# Lights.net
KiCad netlist of a schematic drawn in Altium Designer
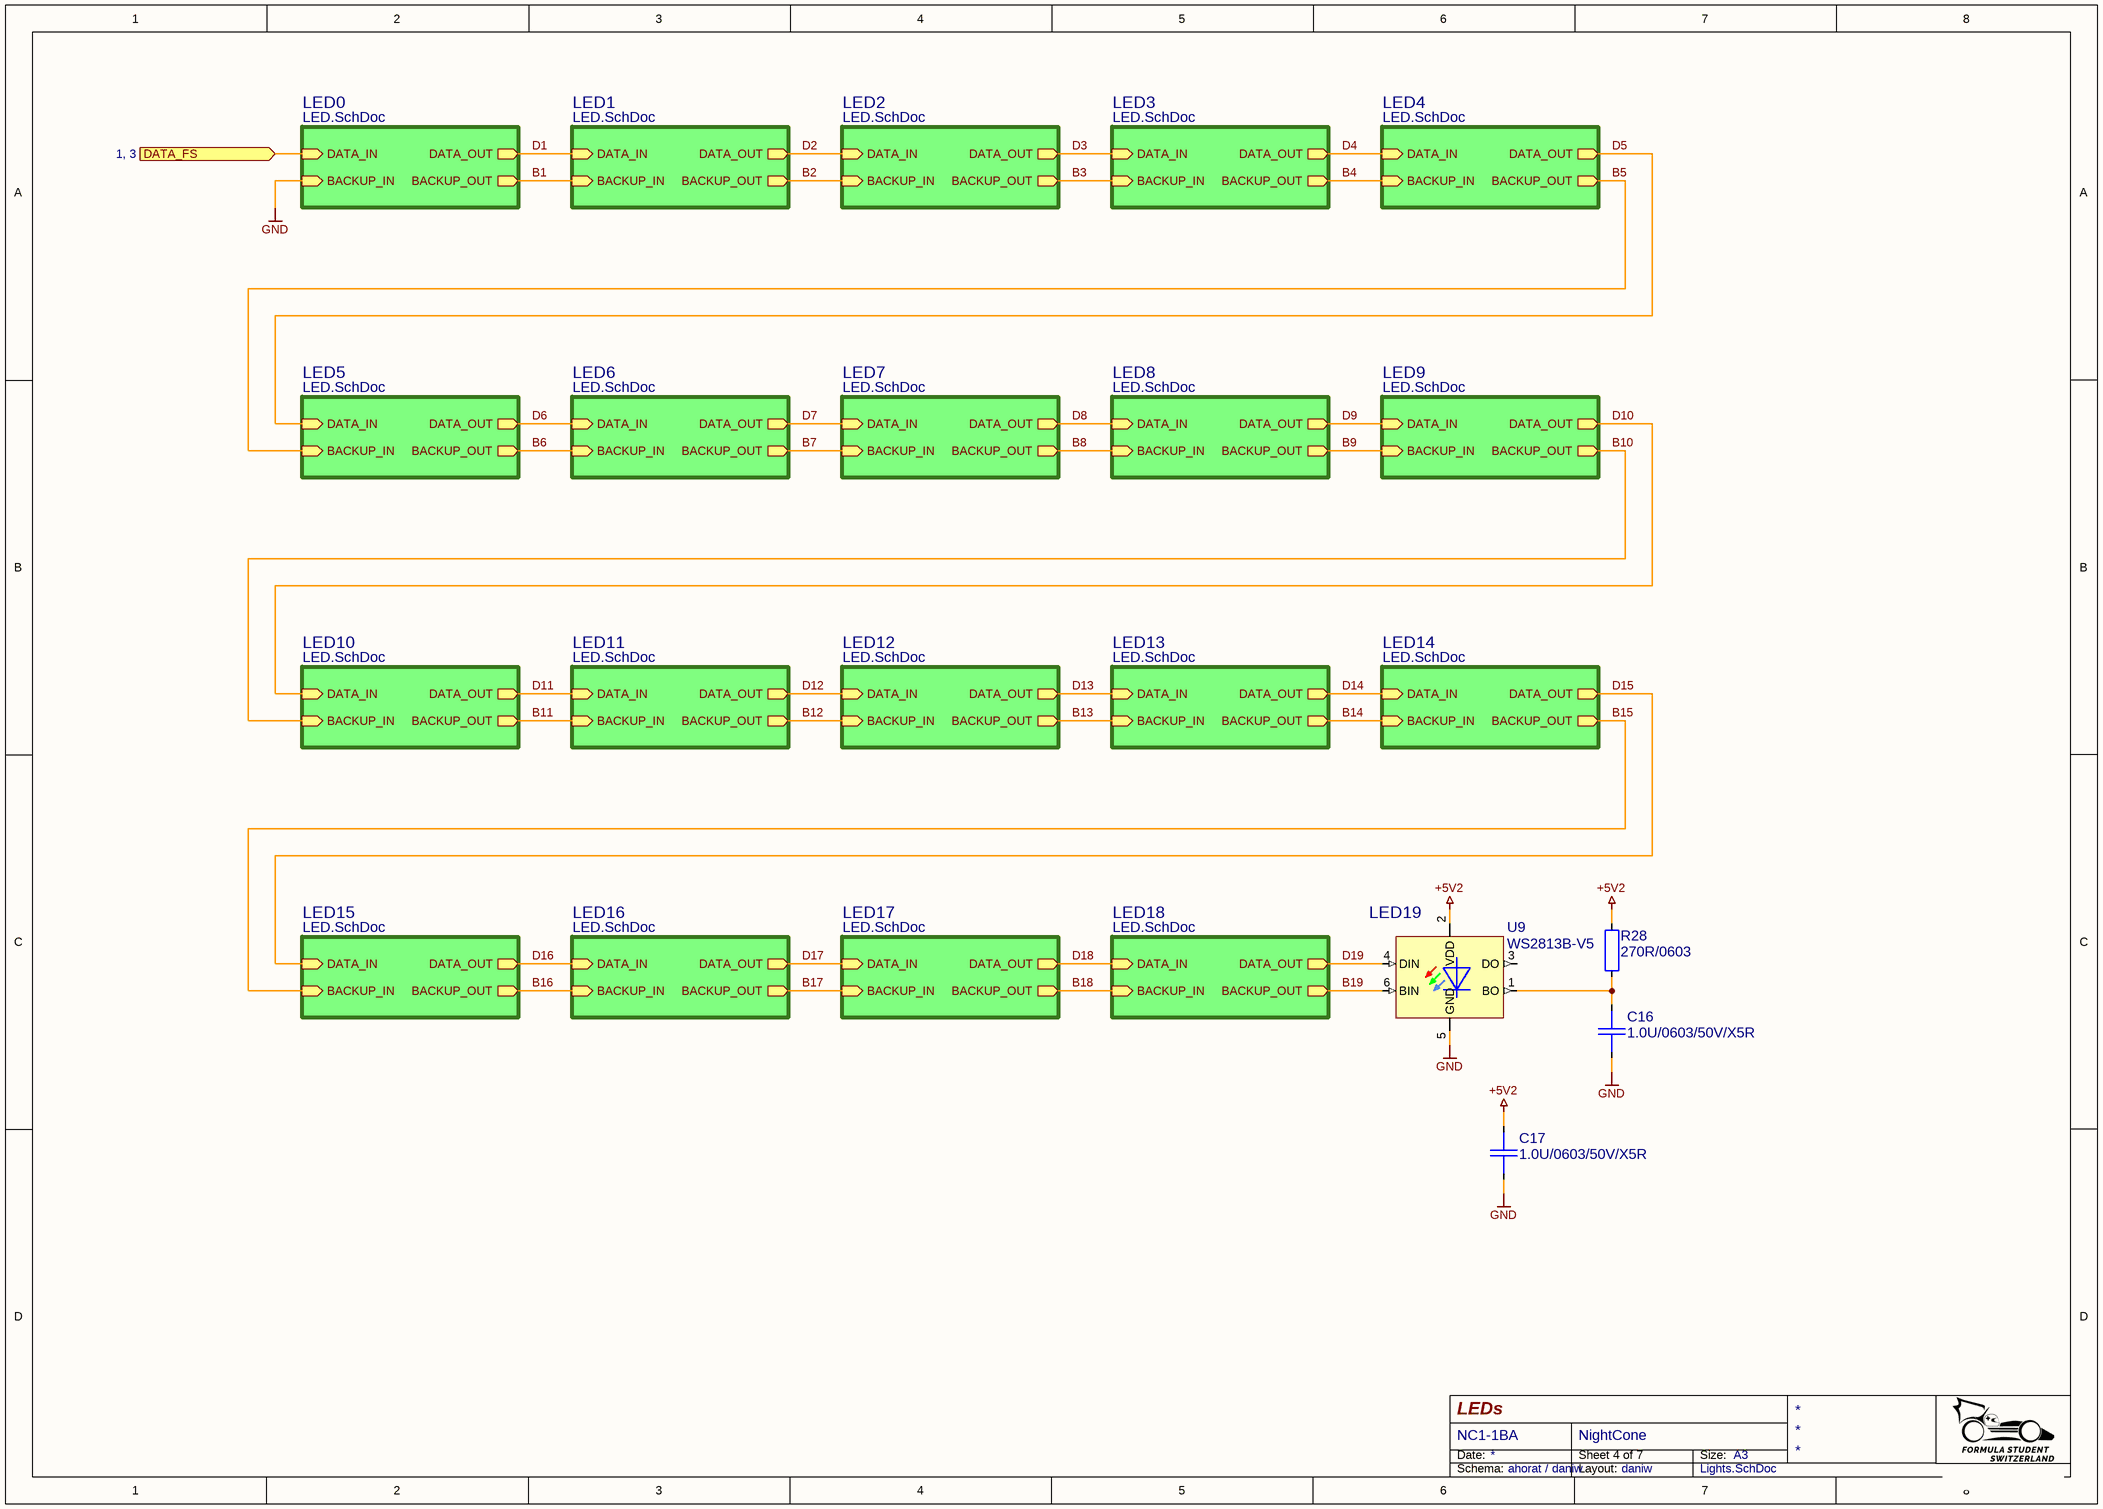
[diagram p0: Lights.SchDoc]

(export (version "E")
  (design (tool "Eeschema 10.0.6"))
  (components
    (comp (ref "C16")
      (value "1.0U/0603/50V/X5R")
      (footprint "CAP0603_X7R")
      (description "CAP SM 0603 1.0uF 50V X5R")
      (fields (field (name "MANUFACTURER") "GENERIC"))
      (libsource (lib "daniw_altium_lib") (part "C"))
    )
    (comp (ref "C17")
      (value "1.0U/0603/50V/X5R")
      (footprint "CAP0603_X7R")
      (description "CAP SM 0603 1.0uF 50V X5R")
      (fields (field (name "MANUFACTURER") "GENERIC"))
      (libsource (lib "daniw_altium_lib") (part "C"))
    )
    (comp (ref "R28")
      (value "270R/0603")
      (footprint "R0603-0.40-WW")
      (description "RES SM 0603 270R")
      (fields (field (name "MANUFACTURER") "GENERIC"))
      (libsource (lib "daniw_altium_lib") (part "R"))
    )
    (comp (ref "U9")
      (value "WS2813B-V5")
      (footprint "LEDM5050X165-6-SE")
      (description "Intelligent control LED integrated light source with backup Pin")
      (fields (field (name "MANUFACTURER") "WorldSemi"))
      (libsource (lib "daniw_altium_lib") (part "WS2813_BO"))
    )
  )
  (nets
    (net (code "1") (name "+5V2") (class "Default")
      (node (ref "C17") (pin "1") (pinfunction "1_1") (pintype "passive"))
      (node (ref "R28") (pin "1") (pinfunction "1_1") (pintype "passive"))
      (node (ref "U9") (pin "2") (pinfunction "VDD_2") (pintype "passive"))
    )
    (net (code "20") (name "/B19") (class "Default")
      (node (ref "U9") (pin "6") (pinfunction "BIN_6") (pintype "input"))
    )
    (net (code "39") (name "/D19") (class "Default")
      (node (ref "U9") (pin "4") (pinfunction "DIN_4") (pintype "input"))
    )
    (net (code "41") (name "GND") (class "Default")
      (node (ref "C16") (pin "2") (pinfunction "2_2") (pintype "passive"))
      (node (ref "C17") (pin "2") (pinfunction "2_2") (pintype "passive"))
      (node (ref "U9") (pin "5") (pinfunction "GND_5") (pintype "passive"))
    )
    (net (code "42") (name "Net-(U9-BO)") (class "Default")
      (node (ref "C16") (pin "1") (pinfunction "1_1") (pintype "passive"))
      (node (ref "R28") (pin "2") (pinfunction "2_2") (pintype "passive"))
      (node (ref "U9") (pin "1") (pinfunction "BO_1") (pintype "output"))
    )
    (net (code "43") (name "unconnected-(U9-DO-Pad3)") (class "Default")
      (node (ref "U9") (pin "3") (pinfunction "DO_3") (pintype "output"))
    )
  )
)
